# MOTOR.net
KiCad netlist of a schematic drawn in EAGLE
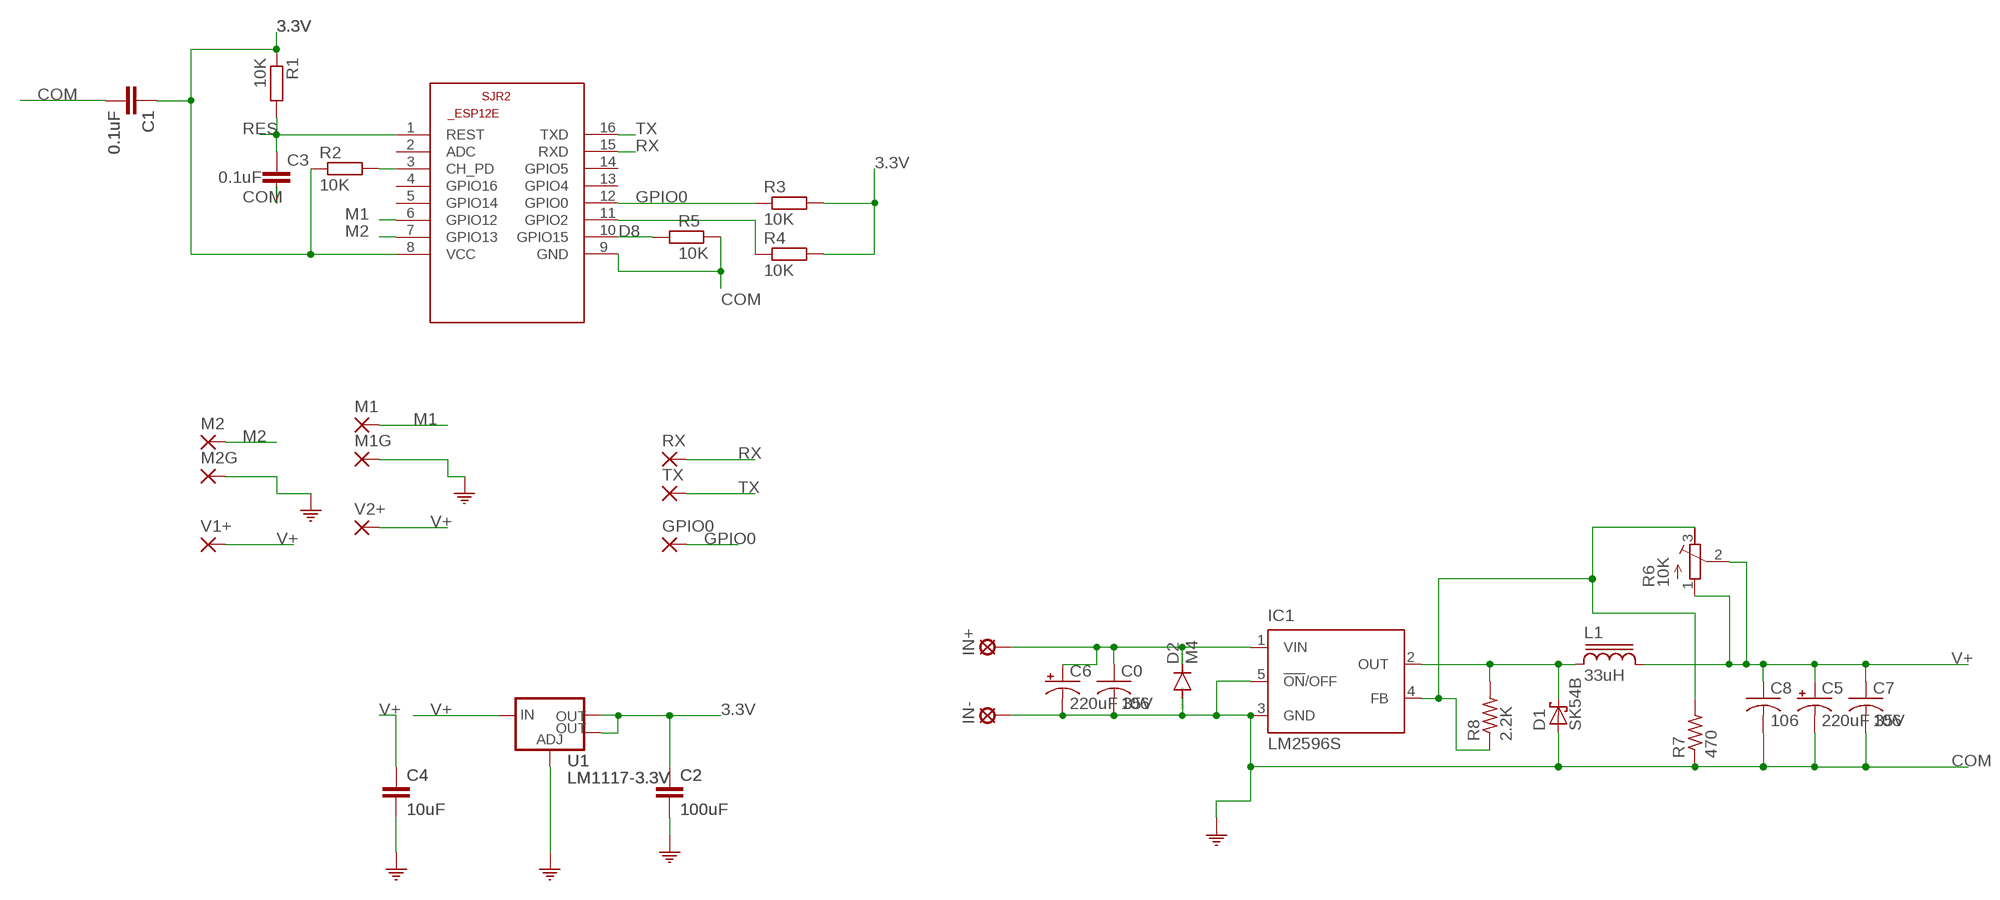
[diagram p0: schematic, sheet 1]

(export (version "E")
  (design (tool "Eeschema 10.0.6"))
  (components
    (comp (ref "C0")
      (value "106")
      (footprint "eagle-import:C1206")
      (libsource (lib "eagle-import") (part "C-USC1206"))
    )
    (comp (ref "C1")
      (value "0.1uF")
      (footprint "eagle-import:C1206")
      (libsource (lib "eagle-import") (part "C-EUC1206"))
    )
    (comp (ref "C2")
      (value "100uF")
      (footprint "eagle-import:C1206")
      (libsource (lib "eagle-import") (part "C-EUC1206"))
    )
    (comp (ref "C3")
      (value "0.1uF")
      (footprint "eagle-import:C1206")
      (libsource (lib "eagle-import") (part "rcl_334_C-EUC1206"))
    )
    (comp (ref "C4")
      (value "10uF")
      (footprint "eagle-import:C1206")
      (libsource (lib "eagle-import") (part "C-EUC1206"))
    )
    (comp (ref "C5")
      (value "220uF 35V")
      (footprint "eagle-import:UD-8X10_NICHICON")
      (libsource (lib "eagle-import") (part "CPOL-USUD-8X10"))
    )
    (comp (ref "C6")
      (value "220uF 35V")
      (footprint "eagle-import:UD-8X10_NICHICON")
      (libsource (lib "eagle-import") (part "CPOL-USUD-8X10"))
    )
    (comp (ref "C7")
      (value "106")
      (footprint "eagle-import:C1206")
      (libsource (lib "eagle-import") (part "C-USC1206"))
    )
    (comp (ref "C8")
      (value "106")
      (footprint "eagle-import:C1206")
      (libsource (lib "eagle-import") (part "C-USC1206"))
    )
    (comp (ref "D1")
      (value "SK54B")
      (footprint "eagle-import:SMB")
      (libsource (lib "eagle-import") (part "SCHOTTKY-DIODESMD"))
    )
    (comp (ref "D2")
      (value "M4")
      (footprint "eagle-import:DO214AC")
      (libsource (lib "eagle-import") (part "DIODE-DO214AC"))
    )
    (comp (ref "GPIO0")
      (value "SMD2")
      (footprint "eagle-import:SMD1,27-2,54")
      (libsource (lib "eagle-import") (part "SMD2"))
    )
    (comp (ref "IC1")
      (value "LM2596S")
      (footprint "eagle-import:TO263-5")
      (fields (field (name "MF") "NATIONAL SEMICONDUCTOR") (field (name "MPN") "LM2596S-ADJ/NOPB"))
      (libsource (lib "eagle-import") (part "LM2596S"))
    )
    (comp (ref "IN+")
      (value "LSP13")
      (footprint "eagle-import:LSP13")
      (libsource (lib "eagle-import") (part "LSP13"))
    )
    (comp (ref "IN-")
      (value "LSP13")
      (footprint "eagle-import:LSP13")
      (libsource (lib "eagle-import") (part "LSP13"))
    )
    (comp (ref "L1")
      (value "33uH")
      (footprint "eagle-import:CDRH127_LD")
      (libsource (lib "eagle-import") (part "CDRH127/LD"))
    )
    (comp (ref "M1")
      (value "SMD2")
      (footprint "eagle-import:SMD1,27-2,54")
      (libsource (lib "eagle-import") (part "SMD2"))
    )
    (comp (ref "M1G")
      (value "SMD2")
      (footprint "eagle-import:SMD1,27-2,54")
      (libsource (lib "eagle-import") (part "SMD2"))
    )
    (comp (ref "M2")
      (value "SMD2")
      (footprint "eagle-import:SMD1,27-2,54")
      (libsource (lib "eagle-import") (part "SMD2"))
    )
    (comp (ref "M2G")
      (value "COM")
      (footprint "eagle-import:SMD1,27-2,54")
      (libsource (lib "eagle-import") (part "SMD2"))
    )
    (comp (ref "R1")
      (value "10K")
      (footprint "eagle-import:R0805")
      (libsource (lib "eagle-import") (part "R-EU_R0805"))
    )
    (comp (ref "R2")
      (value "10K")
      (footprint "eagle-import:R0805")
      (libsource (lib "eagle-import") (part "R-EU_R0805"))
    )
    (comp (ref "R3")
      (value "10K")
      (footprint "eagle-import:R0805")
      (libsource (lib "eagle-import") (part "R-EU_R0805"))
    )
    (comp (ref "R4")
      (value "10K")
      (footprint "eagle-import:R0805")
      (libsource (lib "eagle-import") (part "R-EU_R0805"))
    )
    (comp (ref "R5")
      (value "10K")
      (footprint "eagle-import:R0805")
      (libsource (lib "eagle-import") (part "R-EU_R0805"))
    )
    (comp (ref "R6")
      (value "10K")
      (footprint "eagle-import:RTRIM3296W")
      (libsource (lib "eagle-import") (part "R-TRIMM3296W"))
    )
    (comp (ref "R7")
      (value "470")
      (footprint "eagle-import:R1206")
      (libsource (lib "eagle-import") (part "R-US_R1206"))
    )
    (comp (ref "R8")
      (value "2.2K")
      (footprint "eagle-import:R1206")
      (libsource (lib "eagle-import") (part "R-US_R1206"))
    )
    (comp (ref "RX")
      (value "SMD2")
      (footprint "eagle-import:SMD1,27-2,54")
      (libsource (lib "eagle-import") (part "SMD2"))
    )
    (comp (ref "SJR2")
      (value "ESP8266-12EESP12E")
      (footprint "eagle-import:ESP8266-ESP12E")
      (libsource (lib "eagle-import") (part "ESP8266-12EESP12E"))
    )
    (comp (ref "TX")
      (value "SMD2")
      (footprint "eagle-import:SMD1,27-2,54")
      (libsource (lib "eagle-import") (part "SMD2"))
    )
    (comp (ref "U1")
      (value "LM1117-3.3V")
      (footprint "eagle-import:SOT223")
      (libsource (lib "eagle-import") (part "V_REG_LM1117SOT223"))
    )
    (comp (ref "V1+")
      (value "SMD2")
      (footprint "eagle-import:SMD1,27-2,54")
      (libsource (lib "eagle-import") (part "SMD2"))
    )
    (comp (ref "V2+")
      (value "SMD2")
      (footprint "eagle-import:SMD1,27-2,54")
      (libsource (lib "eagle-import") (part "SMD2"))
    )
  )
  (nets
    (net (code "1") (name "/3.3V") (class "Default")
      (node (ref "C1") (pin "1") (pinfunction "1_1") (pintype "passive"))
      (node (ref "C2") (pin "1") (pinfunction "1_1") (pintype "passive"))
      (node (ref "R1") (pin "1") (pinfunction "1_1") (pintype "passive"))
      (node (ref "R2") (pin "1") (pinfunction "1_1") (pintype "passive"))
      (node (ref "R3") (pin "2") (pinfunction "2_2") (pintype "passive"))
      (node (ref "R4") (pin "2") (pinfunction "2_2") (pintype "passive"))
      (node (ref "SJR2") (pin "8") (pinfunction "VCC_8") (pintype "bidirectional"))
      (node (ref "U1") (pin "2") (pinfunction "OUT_2") (pintype "output"))
      (node (ref "U1") (pin "4") (pinfunction "OUT_4") (pintype "output"))
    )
    (net (code "2") (name "/D8") (class "Default")
      (node (ref "R5") (pin "1") (pinfunction "1_1") (pintype "passive"))
      (node (ref "SJR2") (pin "10") (pinfunction "GPIO15_10") (pintype "bidirectional"))
    )
    (net (code "3") (name "/GPIO0") (class "Default")
      (node (ref "GPIO0") (pin "1") (pinfunction "P_1") (pintype "passive"))
      (node (ref "R3") (pin "1") (pinfunction "1_1") (pintype "passive"))
      (node (ref "SJR2") (pin "12") (pinfunction "GPIO0_12") (pintype "bidirectional"))
    )
    (net (code "4") (name "/M1") (class "Default")
      (node (ref "M1") (pin "1") (pinfunction "P_1") (pintype "passive"))
      (node (ref "SJR2") (pin "6") (pinfunction "GPIO12_6") (pintype "bidirectional"))
    )
    (net (code "5") (name "/M2") (class "Default")
      (node (ref "M2") (pin "1") (pinfunction "P_1") (pintype "passive"))
      (node (ref "SJR2") (pin "7") (pinfunction "GPIO13_7") (pintype "bidirectional"))
    )
    (net (code "6") (name "/RES") (class "Default")
      (node (ref "C3") (pin "1") (pinfunction "1_1") (pintype "passive"))
      (node (ref "R1") (pin "2") (pinfunction "2_2") (pintype "passive"))
      (node (ref "SJR2") (pin "1") (pinfunction "REST_1") (pintype "bidirectional"))
    )
    (net (code "7") (name "/RX") (class "Default")
      (node (ref "RX") (pin "1") (pinfunction "P_1") (pintype "passive"))
      (node (ref "SJR2") (pin "15") (pinfunction "RXD_15") (pintype "bidirectional"))
    )
    (net (code "8") (name "/TX") (class "Default")
      (node (ref "SJR2") (pin "16") (pinfunction "TXD_16") (pintype "bidirectional"))
      (node (ref "TX") (pin "1") (pinfunction "P_1") (pintype "passive"))
    )
    (net (code "9") (name "/V+") (class "Default")
      (node (ref "C4") (pin "1") (pinfunction "1_1") (pintype "passive"))
      (node (ref "C5") (pin "+") (pinfunction "+_+") (pintype "passive"))
      (node (ref "C7") (pin "1") (pinfunction "1_1") (pintype "passive"))
      (node (ref "C8") (pin "1") (pinfunction "1_1") (pintype "passive"))
      (node (ref "L1") (pin "2") (pinfunction "2_2") (pintype "passive"))
      (node (ref "R6") (pin "1") (pinfunction "A_1") (pintype "passive"))
      (node (ref "R6") (pin "2") (pinfunction "S_2") (pintype "passive"))
      (node (ref "U1") (pin "3") (pinfunction "IN_3") (pintype "input"))
      (node (ref "V1+") (pin "1") (pinfunction "P_1") (pintype "passive"))
      (node (ref "V2+") (pin "1") (pinfunction "P_1") (pintype "passive"))
    )
    (net (code "10") (name "COM") (class "Default")
      (node (ref "C0") (pin "2") (pinfunction "2_2") (pintype "passive"))
      (node (ref "C1") (pin "2") (pinfunction "2_2") (pintype "passive"))
      (node (ref "C2") (pin "2") (pinfunction "2_2") (pintype "passive"))
      (node (ref "C3") (pin "2") (pinfunction "2_2") (pintype "passive"))
      (node (ref "C4") (pin "2") (pinfunction "2_2") (pintype "passive"))
      (node (ref "C5") (pin "-") (pinfunction "-_-") (pintype "passive"))
      (node (ref "C6") (pin "-") (pinfunction "-_-") (pintype "passive"))
      (node (ref "C7") (pin "2") (pinfunction "2_2") (pintype "passive"))
      (node (ref "C8") (pin "2") (pinfunction "2_2") (pintype "passive"))
      (node (ref "D1") (pin "A") (pinfunction "A_A") (pintype "passive"))
      (node (ref "D2") (pin "A") (pinfunction "A_A") (pintype "passive"))
      (node (ref "IC1") (pin "3") (pinfunction "GND_3") (pintype "power_in"))
      (node (ref "IC1") (pin "5") (pinfunction "~{ON}/OFF_5") (pintype "input"))
      (node (ref "IN-") (pin "MP") (pinfunction "MP_MP") (pintype "passive"))
      (node (ref "M1G") (pin "1") (pinfunction "P_1") (pintype "passive"))
      (node (ref "M2G") (pin "1") (pinfunction "P_1") (pintype "passive"))
      (node (ref "R5") (pin "2") (pinfunction "2_2") (pintype "passive"))
      (node (ref "R7") (pin "1") (pinfunction "1_1") (pintype "passive"))
      (node (ref "SJR2") (pin "9") (pinfunction "GND_9") (pintype "bidirectional"))
      (node (ref "U1") (pin "1") (pinfunction "ADJ_1") (pintype "input"))
    )
    (net (code "11") (name "Net-(IC1-FB)") (class "Default")
      (node (ref "IC1") (pin "4") (pinfunction "FB_4") (pintype "input"))
      (node (ref "R6") (pin "3") (pinfunction "E_3") (pintype "passive"))
      (node (ref "R7") (pin "2") (pinfunction "2_2") (pintype "passive"))
      (node (ref "R8") (pin "1") (pinfunction "1_1") (pintype "passive"))
    )
    (net (code "12") (name "Net-(IC1-OUT)") (class "Default")
      (node (ref "D1") (pin "C") (pinfunction "C_C") (pintype "passive"))
      (node (ref "IC1") (pin "2") (pinfunction "OUT_2") (pintype "output"))
      (node (ref "L1") (pin "1") (pinfunction "1_1") (pintype "passive"))
      (node (ref "R8") (pin "2") (pinfunction "2_2") (pintype "passive"))
    )
    (net (code "13") (name "Net-(IC1-VIN)") (class "Default")
      (node (ref "C0") (pin "1") (pinfunction "1_1") (pintype "passive"))
      (node (ref "C6") (pin "+") (pinfunction "+_+") (pintype "passive"))
      (node (ref "D2") (pin "C") (pinfunction "C_C") (pintype "passive"))
      (node (ref "IC1") (pin "1") (pinfunction "VIN_1") (pintype "input"))
      (node (ref "IN+") (pin "MP") (pinfunction "MP_MP") (pintype "passive"))
    )
    (net (code "14") (name "Net-(SJR2-CH_PD)") (class "Default")
      (node (ref "R2") (pin "2") (pinfunction "2_2") (pintype "passive"))
      (node (ref "SJR2") (pin "3") (pinfunction "CH_PD_3") (pintype "bidirectional"))
    )
    (net (code "15") (name "Net-(SJR2-GPIO2)") (class "Default")
      (node (ref "R4") (pin "1") (pinfunction "1_1") (pintype "passive"))
      (node (ref "SJR2") (pin "11") (pinfunction "GPIO2_11") (pintype "bidirectional"))
    )
    (net (code "16") (name "unconnected-(SJR2-ADC-Pad2)") (class "Default")
      (node (ref "SJR2") (pin "2") (pinfunction "ADC_2") (pintype "bidirectional"))
    )
    (net (code "17") (name "unconnected-(SJR2-GPIO4-Pad13)") (class "Default")
      (node (ref "SJR2") (pin "13") (pinfunction "GPIO4_13") (pintype "bidirectional"))
    )
    (net (code "18") (name "unconnected-(SJR2-GPIO5-Pad14)") (class "Default")
      (node (ref "SJR2") (pin "14") (pinfunction "GPIO5_14") (pintype "bidirectional"))
    )
    (net (code "19") (name "unconnected-(SJR2-GPIO14-Pad5)") (class "Default")
      (node (ref "SJR2") (pin "5") (pinfunction "GPIO14_5") (pintype "bidirectional"))
    )
    (net (code "20") (name "unconnected-(SJR2-GPIO16-Pad4)") (class "Default")
      (node (ref "SJR2") (pin "4") (pinfunction "GPIO16_4") (pintype "bidirectional"))
    )
  )
)
